# Copy_of_5_and_-5_Supply_Switches.net
KiCad netlist of a schematic drawn in Altium Designer
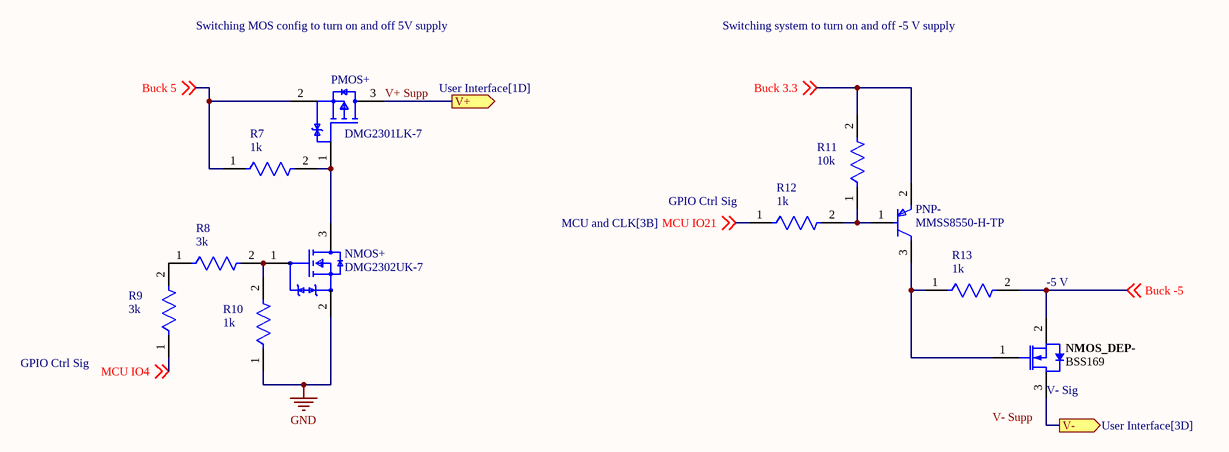
[diagram p0: Copy of 5 and -5 Supply Switches.SchDoc]

(export (version "E")
  (design (tool "Eeschema 10.0.6"))
  (components
    (comp (ref "NMOS+")
      (value "DMG2302UK-7")
      (footprint "FP-SOT23-MFG")
      (description "MOSFET N-CH 20V 2.8A SOT23")
      (fields
        (field (name "OCTOPART") "https://octopart.com/dmg2302uk-7-diodes+inc.-73850182")
        (field (name "MANUFACTURER") "Diodes Inc.")
      )
      (libsource (lib "Altium Content Vault") (part "87c0c04a04979492222792dd46c39c9"))
    )
    (comp (ref "NMOS_DEP-")
      (value "BSS169")
      (footprint "INF-PG-SOT23_N")
      (fields (field (name "MANUFACTURER") "Infineon"))
      (libsource (lib "Altium Content Vault") (part "INF-NDMOS-GSD-3"))
    )
    (comp (ref "PMOS+")
      (value "DMG2301LK-7")
      (footprint "FP-SOT23-IPC_B")
      (description "MOSFET P-CHA 20V 2.4A SOT23")
      (libsource (lib "Altium Content Vault") (part "d2c0d31e441d0c4ace7f3b05f74b3be"))
    )
    (comp (ref "PNP-")
      (value "MMSS8550-H-TP")
      (footprint "FP-SOT-23-IPC_B")
      (description "TRANS PNP 25V 1.5A SOT23")
      (libsource (lib "Altium Content Vault") (part "0e8486ed3b47d9c69b8404ba87cf0f7"))
    )
    (comp (ref "R7")
      (value "1k")
      (footprint "FP-RNCP0805-MFG")
      (description "1kΩ ±1% 0.25W 0805 High Power Anti-Sulfur Thin Film Chip Resistor")
      (fields (field (name "TOLERANCE") "1%"))
      (libsource (lib "Altium Content Vault") (part "1029c3af85768c4190bb7ad29bc67b5"))
    )
    (comp (ref "R8")
      (value "3k")
      (footprint "FP-CR0805-IPC_B")
      (description "Thick Film Chip Resistors 0805 3kΩ 0.125W 1% 100ppm/°C")
      (fields (field (name "TOLERANCE") "1%"))
      (libsource (lib "Altium Content Vault") (part "1029c3af85768c4190bb7ad29bc67b5"))
    )
    (comp (ref "R9")
      (value "3k")
      (footprint "FP-CR0805-IPC_B")
      (description "Thick Film Chip Resistors 0805 3kΩ 0.125W 1% 100ppm/°C")
      (fields (field (name "TOLERANCE") "1%"))
      (libsource (lib "Altium Content Vault") (part "1029c3af85768c4190bb7ad29bc67b5"))
    )
    (comp (ref "R10")
      (value "1k")
      (footprint "FP-RNCP0805-MFG")
      (description "1kΩ ±1% 0.25W 0805 High Power Anti-Sulfur Thin Film Chip Resistor")
      (fields (field (name "TOLERANCE") "1%"))
      (libsource (lib "Altium Content Vault") (part "1029c3af85768c4190bb7ad29bc67b5"))
    )
    (comp (ref "R11")
      (value "10k")
      (footprint "FP-RK73H1J-IPC_B")
      (description "10kΩ ±1% 0.1W Chip Resistor 0603 Thick Film AEC-Q200 Qualified")
      (fields (field (name "TOLERANCE") "1%"))
      (libsource (lib "Altium Content Vault") (part "1029c3af85768c4190bb7ad29bc67b5"))
    )
    (comp (ref "R12")
      (value "1k")
      (footprint "FP-RNCP0805-MFG")
      (description "1kΩ ±1% 0.25W 0805 High Power Anti-Sulfur Thin Film Chip Resistor")
      (fields (field (name "TOLERANCE") "1%"))
      (libsource (lib "Altium Content Vault") (part "1029c3af85768c4190bb7ad29bc67b5"))
    )
    (comp (ref "R13")
      (value "1k")
      (footprint "FP-RNCP0805-MFG")
      (description "1kΩ ±1% 0.25W 0805 High Power Anti-Sulfur Thin Film Chip Resistor")
      (fields (field (name "TOLERANCE") "1%"))
      (libsource (lib "Altium Content Vault") (part "1029c3af85768c4190bb7ad29bc67b5"))
    )
  )
  (nets
    (net (code "1") (name "/V+ Supp") (class "Default")
      (node (ref "PMOS+") (pin "3") (pinfunction "D_3") (pintype "passive"))
    )
    (net (code "2") (name "/V-") (class "Default")
      (node (ref "NMOS_DEP-") (pin "3") (pinfunction "DRAIN_3") (pintype "passive"))
    )
    (net (code "4") (name "Buck -5") (class "Default")
      (node (ref "NMOS_DEP-") (pin "2") (pinfunction "SOURCE_2") (pintype "passive"))
      (node (ref "R13") (pin "2") (pinfunction "2_2") (pintype "passive"))
    )
    (net (code "5") (name "Buck 3.3") (class "Default")
      (node (ref "PNP-") (pin "2") (pinfunction "E_2") (pintype "passive"))
      (node (ref "R11") (pin "2") (pinfunction "2_2") (pintype "passive"))
    )
    (net (code "6") (name "Buck 5") (class "Default")
      (node (ref "PMOS+") (pin "2") (pinfunction "S_2") (pintype "passive"))
      (node (ref "R7") (pin "1") (pinfunction "1_1") (pintype "passive"))
    )
    (net (code "7") (name "GND") (class "Default")
      (node (ref "NMOS+") (pin "2") (pinfunction "S_2") (pintype "passive"))
      (node (ref "R10") (pin "1") (pinfunction "1_1") (pintype "passive"))
    )
    (net (code "8") (name "MCU IO4") (class "Default")
      (node (ref "R9") (pin "1") (pinfunction "1_1") (pintype "passive"))
    )
    (net (code "9") (name "MCU IO21") (class "Default")
      (node (ref "R12") (pin "1") (pinfunction "1_1") (pintype "passive"))
    )
    (net (code "10") (name "Net-(NMOS+-D)") (class "Default")
      (node (ref "NMOS+") (pin "3") (pinfunction "D_3") (pintype "passive"))
      (node (ref "PMOS+") (pin "1") (pinfunction "G_1") (pintype "passive"))
      (node (ref "R7") (pin "2") (pinfunction "2_2") (pintype "passive"))
    )
    (net (code "11") (name "Net-(NMOS+-G)") (class "Default")
      (node (ref "NMOS+") (pin "1") (pinfunction "G_1") (pintype "passive"))
      (node (ref "R10") (pin "2") (pinfunction "2_2") (pintype "passive"))
      (node (ref "R8") (pin "2") (pinfunction "2_2") (pintype "passive"))
    )
    (net (code "12") (name "Net-(NMOS_DEP--GATE)") (class "Default")
      (node (ref "NMOS_DEP-") (pin "1") (pinfunction "GATE_1") (pintype "passive"))
      (node (ref "PNP-") (pin "3") (pinfunction "C_3") (pintype "passive"))
      (node (ref "R13") (pin "1") (pinfunction "1_1") (pintype "passive"))
    )
    (net (code "13") (name "Net-(PNP--B)") (class "Default")
      (node (ref "PNP-") (pin "1") (pinfunction "B_1") (pintype "passive"))
      (node (ref "R11") (pin "1") (pinfunction "1_1") (pintype "passive"))
      (node (ref "R12") (pin "2") (pinfunction "2_2") (pintype "passive"))
    )
    (net (code "14") (name "Net-(R8-Pad1)") (class "Default")
      (node (ref "R8") (pin "1") (pinfunction "1_1") (pintype "passive"))
      (node (ref "R9") (pin "2") (pinfunction "2_2") (pintype "passive"))
    )
  )
)
